# ExtensionConnector.net
KiCad netlist of a schematic drawn in Altium Designer
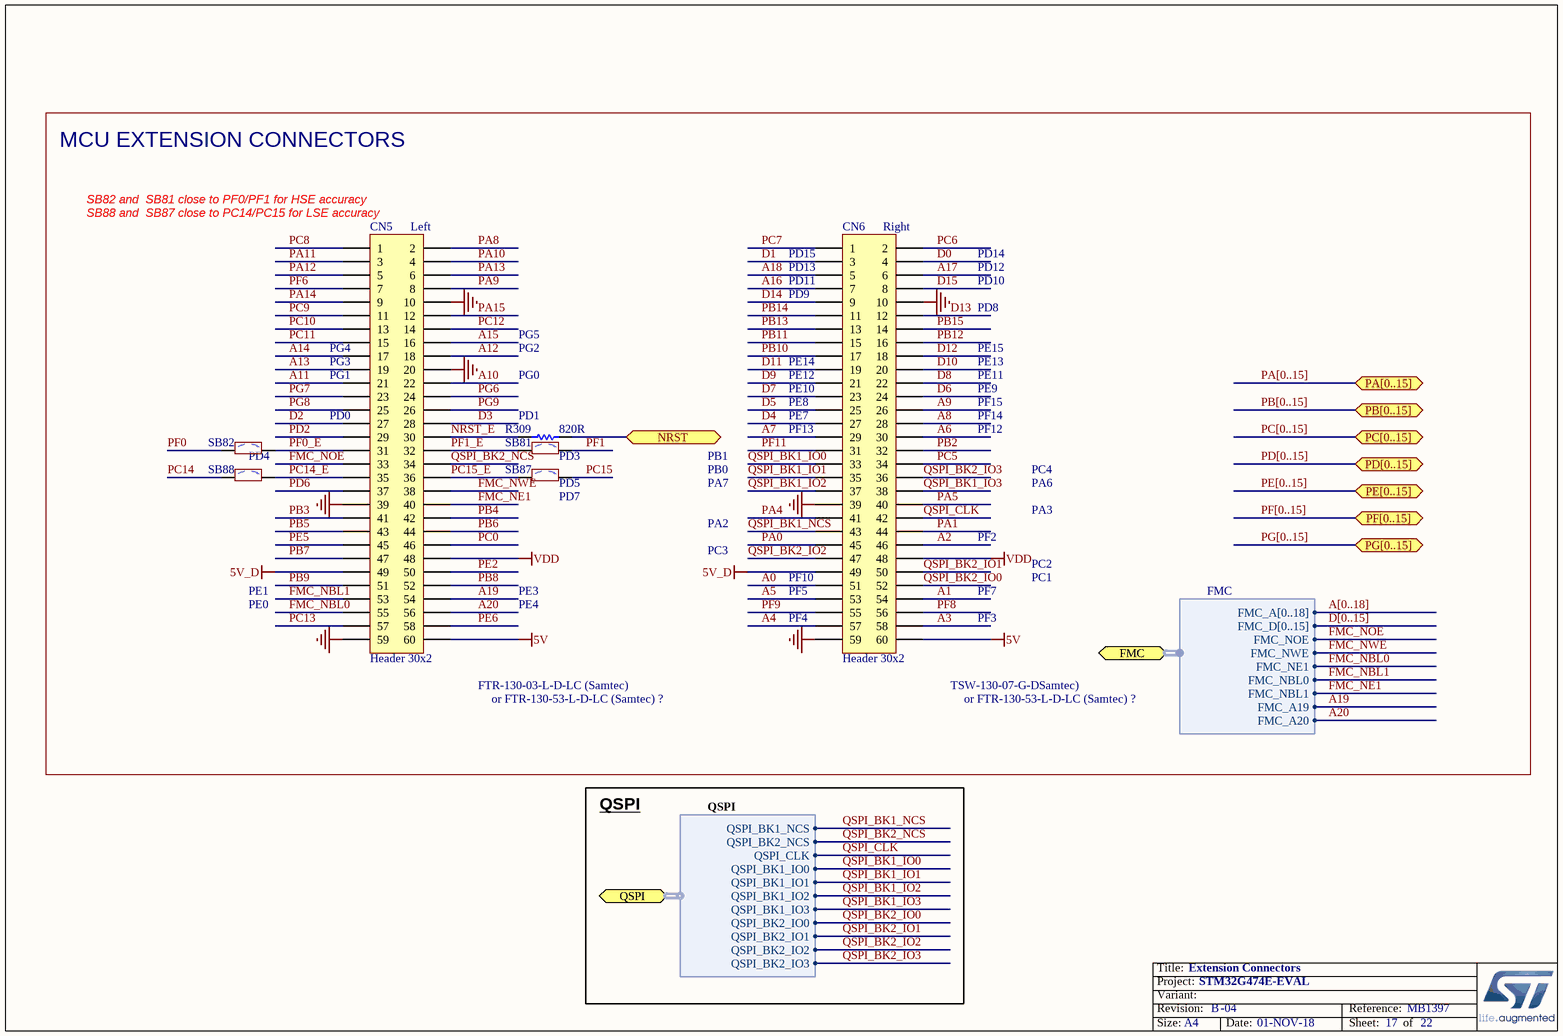
[diagram p0: ExtensionConnector.SchDoc]

(export (version "E")
  (design (tool "Eeschema 10.0.6"))
  (components
    (comp (ref "CN5")
      (value "Header 30x2")
      (footprint "CON_SAMTEC_FTR-130-53-L-D-LC")
      (description "Header 30x2, 1.27mm, VR, CMS, Height 7.24mm")
      (fields
        (field (name "INTERNAL_PART_NUMBER") "MCD-00576")
        (field (name "MANUFACTURER_PART_NUMBER") "FTR-130-53-L-D-LC")
        (field (name "PROVIDED_BY") "SUBCO")
      )
      (libsource (lib "MCD_PARTS_database") (part "Header 30x2"))
    )
    (comp (ref "CN6")
      (value "Header 30x2")
      (footprint "CON_SAMTEC_FTR-130-53-L-D-LC")
      (description "Header 30x2, 1.27mm, VR, CMS, Height 7.24mm")
      (fields
        (field (name "INTERNAL_PART_NUMBER") "MCD-00576")
        (field (name "MANUFACTURER_PART_NUMBER") "FTR-130-53-L-D-LC")
        (field (name "PROVIDED_BY") "SUBCO")
      )
      (libsource (lib "MCD_PARTS_database") (part "Header 30x2"))
    )
    (comp (ref "R309")
      (value "820R")
      (footprint "R0402")
      (description "Resistor,820R,0402,1%,1/16W")
      (fields
        (field (name "INTERNAL_PART_NUMBER") "MCD-00527")
        (field (name "MANUFACTURER_PART_NUMBER") "RC0402FR-07820RL")
        (field (name "PROVIDED_BY") "SUBCO")
      )
      (libsource (lib "MCD_PARTS_database") (part "Resistor"))
    )
    (comp (ref "SB81")
      (value "SB_OFF")
      (footprint "SOLDER-BRIDGE_R0603-0R")
      (description "Solder Bridge OFF")
      (fields
        (field (name "INTERNAL_PART_NUMBER") "MCD-00072")
        (field (name "MANUFACTURER_PART_NUMBER") "RC0603JR-070RL")
        (field (name "PROVIDED_BY") "SUBCO")
      )
      (libsource (lib "MCD_PARTS_database") (part "SB_OFF"))
    )
    (comp (ref "SB82")
      (value "SB_OFF")
      (footprint "SOLDER-BRIDGE_R0603-0R")
      (description "Solder Bridge OFF")
      (fields
        (field (name "INTERNAL_PART_NUMBER") "MCD-00072")
        (field (name "MANUFACTURER_PART_NUMBER") "RC0603JR-070RL")
        (field (name "PROVIDED_BY") "SUBCO")
      )
      (libsource (lib "MCD_PARTS_database") (part "SB_OFF"))
    )
    (comp (ref "SB87")
      (value "SB_OFF")
      (footprint "SOLDER-BRIDGE_R0603-0R")
      (description "Solder Bridge OFF")
      (fields
        (field (name "INTERNAL_PART_NUMBER") "MCD-00072")
        (field (name "MANUFACTURER_PART_NUMBER") "RC0603JR-070RL")
        (field (name "PROVIDED_BY") "SUBCO")
      )
      (libsource (lib "MCD_PARTS_database") (part "SB_OFF"))
    )
    (comp (ref "SB88")
      (value "SB_OFF")
      (footprint "SOLDER-BRIDGE_R0603-0R")
      (description "Solder Bridge OFF")
      (fields
        (field (name "INTERNAL_PART_NUMBER") "MCD-00072")
        (field (name "MANUFACTURER_PART_NUMBER") "RC0603JR-070RL")
        (field (name "PROVIDED_BY") "SUBCO")
      )
      (libsource (lib "MCD_PARTS_database") (part "SB_OFF"))
    )
  )
  (nets
    (net (code "62") (name "/A0") (class "Default")
      (node (ref "CN6") (pin "51") (pinfunction "51_51") (pintype "passive"))
    )
    (net (code "63") (name "/A1") (class "Default")
      (node (ref "CN6") (pin "54") (pinfunction "54_54") (pintype "passive"))
    )
    (net (code "64") (name "/A2") (class "Default")
      (node (ref "CN6") (pin "46") (pinfunction "46_46") (pintype "passive"))
    )
    (net (code "65") (name "/A3") (class "Default")
      (node (ref "CN6") (pin "58") (pinfunction "58_58") (pintype "passive"))
    )
    (net (code "66") (name "/A4") (class "Default")
      (node (ref "CN6") (pin "57") (pinfunction "57_57") (pintype "passive"))
    )
    (net (code "67") (name "/A5") (class "Default")
      (node (ref "CN6") (pin "53") (pinfunction "53_53") (pintype "passive"))
    )
    (net (code "68") (name "/A6") (class "Default")
      (node (ref "CN6") (pin "30") (pinfunction "30_30") (pintype "passive"))
    )
    (net (code "69") (name "/A7") (class "Default")
      (node (ref "CN6") (pin "29") (pinfunction "29_29") (pintype "passive"))
    )
    (net (code "70") (name "/A8") (class "Default")
      (node (ref "CN6") (pin "28") (pinfunction "28_28") (pintype "passive"))
    )
    (net (code "71") (name "/A9") (class "Default")
      (node (ref "CN6") (pin "26") (pinfunction "26_26") (pintype "passive"))
    )
    (net (code "72") (name "/A10") (class "Default")
      (node (ref "CN5") (pin "22") (pinfunction "22_22") (pintype "passive"))
    )
    (net (code "73") (name "/A11") (class "Default")
      (node (ref "CN5") (pin "21") (pinfunction "21_21") (pintype "passive"))
    )
    (net (code "74") (name "/A12") (class "Default")
      (node (ref "CN5") (pin "18") (pinfunction "18_18") (pintype "passive"))
    )
    (net (code "75") (name "/A13") (class "Default")
      (node (ref "CN5") (pin "19") (pinfunction "19_19") (pintype "passive"))
    )
    (net (code "76") (name "/A14") (class "Default")
      (node (ref "CN5") (pin "17") (pinfunction "17_17") (pintype "passive"))
    )
    (net (code "77") (name "/A15") (class "Default")
      (node (ref "CN5") (pin "16") (pinfunction "16_16") (pintype "passive"))
    )
    (net (code "78") (name "/A16") (class "Default")
      (node (ref "CN6") (pin "7") (pinfunction "7_7") (pintype "passive"))
    )
    (net (code "79") (name "/A17") (class "Default")
      (node (ref "CN6") (pin "6") (pinfunction "6_6") (pintype "passive"))
    )
    (net (code "80") (name "/A18") (class "Default")
      (node (ref "CN6") (pin "5") (pinfunction "5_5") (pintype "passive"))
    )
    (net (code "81") (name "/A19") (class "Default")
      (node (ref "CN5") (pin "54") (pinfunction "54_54") (pintype "passive"))
    )
    (net (code "82") (name "/A20") (class "Default")
      (node (ref "CN5") (pin "56") (pinfunction "56_56") (pintype "passive"))
    )
    (net (code "84") (name "/D0") (class "Default")
      (node (ref "CN6") (pin "4") (pinfunction "4_4") (pintype "passive"))
    )
    (net (code "85") (name "/D1") (class "Default")
      (node (ref "CN6") (pin "3") (pinfunction "3_3") (pintype "passive"))
    )
    (net (code "86") (name "/D2") (class "Default")
      (node (ref "CN5") (pin "27") (pinfunction "27_27") (pintype "passive"))
    )
    (net (code "87") (name "/D3") (class "Default")
      (node (ref "CN5") (pin "28") (pinfunction "28_28") (pintype "passive"))
    )
    (net (code "88") (name "/D4") (class "Default")
      (node (ref "CN6") (pin "27") (pinfunction "27_27") (pintype "passive"))
    )
    (net (code "89") (name "/D5") (class "Default")
      (node (ref "CN6") (pin "25") (pinfunction "25_25") (pintype "passive"))
    )
    (net (code "90") (name "/D6") (class "Default")
      (node (ref "CN6") (pin "24") (pinfunction "24_24") (pintype "passive"))
    )
    (net (code "91") (name "/D7") (class "Default")
      (node (ref "CN6") (pin "23") (pinfunction "23_23") (pintype "passive"))
    )
    (net (code "92") (name "/D8") (class "Default")
      (node (ref "CN6") (pin "22") (pinfunction "22_22") (pintype "passive"))
    )
    (net (code "93") (name "/D9") (class "Default")
      (node (ref "CN6") (pin "21") (pinfunction "21_21") (pintype "passive"))
    )
    (net (code "94") (name "/D10") (class "Default")
      (node (ref "CN6") (pin "20") (pinfunction "20_20") (pintype "passive"))
    )
    (net (code "95") (name "/D11") (class "Default")
      (node (ref "CN6") (pin "19") (pinfunction "19_19") (pintype "passive"))
    )
    (net (code "96") (name "/D12") (class "Default")
      (node (ref "CN6") (pin "18") (pinfunction "18_18") (pintype "passive"))
    )
    (net (code "97") (name "/D13") (class "Default")
      (node (ref "CN6") (pin "12") (pinfunction "12_12") (pintype "passive"))
    )
    (net (code "98") (name "/D14") (class "Default")
      (node (ref "CN6") (pin "9") (pinfunction "9_9") (pintype "passive"))
    )
    (net (code "99") (name "/D15") (class "Default")
      (node (ref "CN6") (pin "8") (pinfunction "8_8") (pintype "passive"))
    )
    (net (code "101") (name "/FMC_NBL0") (class "Default")
      (node (ref "CN5") (pin "55") (pinfunction "55_55") (pintype "passive"))
    )
    (net (code "102") (name "/FMC_NBL1") (class "Default")
      (node (ref "CN5") (pin "53") (pinfunction "53_53") (pintype "passive"))
    )
    (net (code "103") (name "/FMC_NE1") (class "Default")
      (node (ref "CN5") (pin "40") (pinfunction "40_40") (pintype "passive"))
    )
    (net (code "104") (name "/FMC_NOE") (class "Default")
      (node (ref "CN5") (pin "33") (pinfunction "33_33") (pintype "passive"))
    )
    (net (code "105") (name "/FMC_NWE") (class "Default")
      (node (ref "CN5") (pin "38") (pinfunction "38_38") (pintype "passive"))
    )
    (net (code "106") (name "/NRST") (class "Default")
      (node (ref "R309") (pin "2") (pinfunction "2_2") (pintype "passive"))
    )
    (net (code "107") (name "/NRST_E") (class "Default")
      (node (ref "CN5") (pin "30") (pinfunction "30_30") (pintype "passive"))
      (node (ref "R309") (pin "1") (pinfunction "1_1") (pintype "passive"))
    )
    (net (code "108") (name "/PA0") (class "Default")
      (node (ref "CN6") (pin "45") (pinfunction "45_45") (pintype "passive"))
    )
    (net (code "109") (name "/PA1") (class "Default")
      (node (ref "CN6") (pin "44") (pinfunction "44_44") (pintype "passive"))
    )
    (net (code "110") (name "/PA4") (class "Default")
      (node (ref "CN6") (pin "41") (pinfunction "41_41") (pintype "passive"))
    )
    (net (code "111") (name "/PA5") (class "Default")
      (node (ref "CN6") (pin "40") (pinfunction "40_40") (pintype "passive"))
    )
    (net (code "112") (name "/PA8") (class "Default")
      (node (ref "CN5") (pin "2") (pinfunction "2_2") (pintype "passive"))
    )
    (net (code "113") (name "/PA9") (class "Default")
      (node (ref "CN5") (pin "8") (pinfunction "8_8") (pintype "passive"))
    )
    (net (code "114") (name "/PA10") (class "Default")
      (node (ref "CN5") (pin "4") (pinfunction "4_4") (pintype "passive"))
    )
    (net (code "115") (name "/PA11") (class "Default")
      (node (ref "CN5") (pin "3") (pinfunction "3_3") (pintype "passive"))
    )
    (net (code "116") (name "/PA12") (class "Default")
      (node (ref "CN5") (pin "5") (pinfunction "5_5") (pintype "passive"))
    )
    (net (code "117") (name "/PA13") (class "Default")
      (node (ref "CN5") (pin "6") (pinfunction "6_6") (pintype "passive"))
    )
    (net (code "118") (name "/PA14") (class "Default")
      (node (ref "CN5") (pin "9") (pinfunction "9_9") (pintype "passive"))
    )
    (net (code "119") (name "/PA15") (class "Default")
      (node (ref "CN5") (pin "12") (pinfunction "12_12") (pintype "passive"))
    )
    (net (code "121") (name "/PB2") (class "Default")
      (node (ref "CN6") (pin "32") (pinfunction "32_32") (pintype "passive"))
    )
    (net (code "122") (name "/PB3") (class "Default")
      (node (ref "CN5") (pin "41") (pinfunction "41_41") (pintype "passive"))
    )
    (net (code "123") (name "/PB4") (class "Default")
      (node (ref "CN5") (pin "42") (pinfunction "42_42") (pintype "passive"))
    )
    (net (code "124") (name "/PB5") (class "Default")
      (node (ref "CN5") (pin "43") (pinfunction "43_43") (pintype "passive"))
    )
    (net (code "125") (name "/PB6") (class "Default")
      (node (ref "CN5") (pin "44") (pinfunction "44_44") (pintype "passive"))
    )
    (net (code "126") (name "/PB7") (class "Default")
      (node (ref "CN5") (pin "47") (pinfunction "47_47") (pintype "passive"))
    )
    (net (code "127") (name "/PB8") (class "Default")
      (node (ref "CN5") (pin "52") (pinfunction "52_52") (pintype "passive"))
    )
    (net (code "128") (name "/PB9") (class "Default")
      (node (ref "CN5") (pin "51") (pinfunction "51_51") (pintype "passive"))
    )
    (net (code "129") (name "/PB10") (class "Default")
      (node (ref "CN6") (pin "17") (pinfunction "17_17") (pintype "passive"))
    )
    (net (code "130") (name "/PB11") (class "Default")
      (node (ref "CN6") (pin "15") (pinfunction "15_15") (pintype "passive"))
    )
    (net (code "131") (name "/PB12") (class "Default")
      (node (ref "CN6") (pin "16") (pinfunction "16_16") (pintype "passive"))
    )
    (net (code "132") (name "/PB13") (class "Default")
      (node (ref "CN6") (pin "13") (pinfunction "13_13") (pintype "passive"))
    )
    (net (code "133") (name "/PB14") (class "Default")
      (node (ref "CN6") (pin "11") (pinfunction "11_11") (pintype "passive"))
    )
    (net (code "134") (name "/PB15") (class "Default")
      (node (ref "CN6") (pin "14") (pinfunction "14_14") (pintype "passive"))
    )
    (net (code "136") (name "/PC0") (class "Default")
      (node (ref "CN5") (pin "46") (pinfunction "46_46") (pintype "passive"))
    )
    (net (code "137") (name "/PC5") (class "Default")
      (node (ref "CN6") (pin "34") (pinfunction "34_34") (pintype "passive"))
    )
    (net (code "138") (name "/PC6") (class "Default")
      (node (ref "CN6") (pin "2") (pinfunction "2_2") (pintype "passive"))
    )
    (net (code "139") (name "/PC7") (class "Default")
      (node (ref "CN6") (pin "1") (pinfunction "1_1") (pintype "passive"))
    )
    (net (code "140") (name "/PC8") (class "Default")
      (node (ref "CN5") (pin "1") (pinfunction "1_1") (pintype "passive"))
    )
    (net (code "141") (name "/PC9") (class "Default")
      (node (ref "CN5") (pin "11") (pinfunction "11_11") (pintype "passive"))
    )
    (net (code "142") (name "/PC10") (class "Default")
      (node (ref "CN5") (pin "13") (pinfunction "13_13") (pintype "passive"))
    )
    (net (code "143") (name "/PC11") (class "Default")
      (node (ref "CN5") (pin "15") (pinfunction "15_15") (pintype "passive"))
    )
    (net (code "144") (name "/PC12") (class "Default")
      (node (ref "CN5") (pin "14") (pinfunction "14_14") (pintype "passive"))
    )
    (net (code "145") (name "/PC13") (class "Default")
      (node (ref "CN5") (pin "57") (pinfunction "57_57") (pintype "passive"))
    )
    (net (code "146") (name "/PC14") (class "Default")
      (node (ref "SB88") (pin "1") (pinfunction "1_1") (pintype "passive"))
    )
    (net (code "147") (name "/PC14_E") (class "Default")
      (node (ref "CN5") (pin "35") (pinfunction "35_35") (pintype "passive"))
      (node (ref "SB88") (pin "2") (pinfunction "2_2") (pintype "passive"))
    )
    (net (code "148") (name "/PC15") (class "Default")
      (node (ref "SB87") (pin "2") (pinfunction "2_2") (pintype "passive"))
    )
    (net (code "149") (name "/PC15_E") (class "Default")
      (node (ref "CN5") (pin "36") (pinfunction "36_36") (pintype "passive"))
      (node (ref "SB87") (pin "1") (pinfunction "1_1") (pintype "passive"))
    )
    (net (code "151") (name "/PD2") (class "Default")
      (node (ref "CN5") (pin "29") (pinfunction "29_29") (pintype "passive"))
    )
    (net (code "152") (name "/PD6") (class "Default")
      (node (ref "CN5") (pin "37") (pinfunction "37_37") (pintype "passive"))
    )
    (net (code "154") (name "/PE2") (class "Default")
      (node (ref "CN5") (pin "50") (pinfunction "50_50") (pintype "passive"))
    )
    (net (code "155") (name "/PE5") (class "Default")
      (node (ref "CN5") (pin "45") (pinfunction "45_45") (pintype "passive"))
    )
    (net (code "156") (name "/PE6") (class "Default")
      (node (ref "CN5") (pin "58") (pinfunction "58_58") (pintype "passive"))
    )
    (net (code "158") (name "/PF0") (class "Default")
      (node (ref "SB82") (pin "1") (pinfunction "1_1") (pintype "passive"))
    )
    (net (code "159") (name "/PF0_E") (class "Default")
      (node (ref "CN5") (pin "31") (pinfunction "31_31") (pintype "passive"))
      (node (ref "SB82") (pin "2") (pinfunction "2_2") (pintype "passive"))
    )
    (net (code "160") (name "/PF1") (class "Default")
      (node (ref "SB81") (pin "2") (pinfunction "2_2") (pintype "passive"))
    )
    (net (code "161") (name "/PF1_E") (class "Default")
      (node (ref "CN5") (pin "32") (pinfunction "32_32") (pintype "passive"))
      (node (ref "SB81") (pin "1") (pinfunction "1_1") (pintype "passive"))
    )
    (net (code "162") (name "/PF6") (class "Default")
      (node (ref "CN5") (pin "7") (pinfunction "7_7") (pintype "passive"))
    )
    (net (code "163") (name "/PF8") (class "Default")
      (node (ref "CN6") (pin "56") (pinfunction "56_56") (pintype "passive"))
    )
    (net (code "164") (name "/PF9") (class "Default")
      (node (ref "CN6") (pin "55") (pinfunction "55_55") (pintype "passive"))
    )
    (net (code "165") (name "/PF11") (class "Default")
      (node (ref "CN6") (pin "31") (pinfunction "31_31") (pintype "passive"))
    )
    (net (code "167") (name "/PG6") (class "Default")
      (node (ref "CN5") (pin "24") (pinfunction "24_24") (pintype "passive"))
    )
    (net (code "168") (name "/PG7") (class "Default")
      (node (ref "CN5") (pin "23") (pinfunction "23_23") (pintype "passive"))
    )
    (net (code "169") (name "/PG8") (class "Default")
      (node (ref "CN5") (pin "25") (pinfunction "25_25") (pintype "passive"))
    )
    (net (code "170") (name "/PG9") (class "Default")
      (node (ref "CN5") (pin "26") (pinfunction "26_26") (pintype "passive"))
    )
    (net (code "172") (name "/QSPI_BK1_IO0") (class "Default")
      (node (ref "CN6") (pin "33") (pinfunction "33_33") (pintype "passive"))
    )
    (net (code "173") (name "/QSPI_BK1_IO1") (class "Default")
      (node (ref "CN6") (pin "35") (pinfunction "35_35") (pintype "passive"))
    )
    (net (code "174") (name "/QSPI_BK1_IO2") (class "Default")
      (node (ref "CN6") (pin "37") (pinfunction "37_37") (pintype "passive"))
    )
    (net (code "175") (name "/QSPI_BK1_IO3") (class "Default")
      (node (ref "CN6") (pin "38") (pinfunction "38_38") (pintype "passive"))
    )
    (net (code "176") (name "/QSPI_BK1_NCS") (class "Default")
      (node (ref "CN6") (pin "43") (pinfunction "43_43") (pintype "passive"))
    )
    (net (code "177") (name "/QSPI_BK2_IO0") (class "Default")
      (node (ref "CN6") (pin "52") (pinfunction "52_52") (pintype "passive"))
    )
    (net (code "178") (name "/QSPI_BK2_IO1") (class "Default")
      (node (ref "CN6") (pin "50") (pinfunction "50_50") (pintype "passive"))
    )
    (net (code "179") (name "/QSPI_BK2_IO2") (class "Default")
      (node (ref "CN6") (pin "47") (pinfunction "47_47") (pintype "passive"))
    )
    (net (code "180") (name "/QSPI_BK2_IO3") (class "Default")
      (node (ref "CN6") (pin "36") (pinfunction "36_36") (pintype "passive"))
    )
    (net (code "181") (name "/QSPI_BK2_NCS") (class "Default")
      (node (ref "CN5") (pin "34") (pinfunction "34_34") (pintype "passive"))
    )
    (net (code "182") (name "/QSPI_CLK") (class "Default")
      (node (ref "CN6") (pin "42") (pinfunction "42_42") (pintype "passive"))
    )
    (net (code "185") (name "5V") (class "Default")
      (node (ref "CN5") (pin "60") (pinfunction "60_60") (pintype "passive"))
      (node (ref "CN6") (pin "60") (pinfunction "60_60") (pintype "passive"))
    )
    (net (code "186") (name "5V_D") (class "Default")
      (node (ref "CN5") (pin "49") (pinfunction "49_49") (pintype "passive"))
      (node (ref "CN6") (pin "49") (pinfunction "49_49") (pintype "passive"))
    )
    (net (code "187") (name "GND") (class "Default")
      (node (ref "CN5") (pin "10") (pinfunction "10_10") (pintype "passive"))
      (node (ref "CN5") (pin "20") (pinfunction "20_20") (pintype "passive"))
      (node (ref "CN5") (pin "39") (pinfunction "39_39") (pintype "passive"))
      (node (ref "CN5") (pin "59") (pinfunction "59_59") (pintype "passive"))
      (node (ref "CN6") (pin "10") (pinfunction "10_10") (pintype "passive"))
      (node (ref "CN6") (pin "39") (pinfunction "39_39") (pintype "passive"))
      (node (ref "CN6") (pin "59") (pinfunction "59_59") (pintype "passive"))
    )
    (net (code "188") (name "VDD") (class "Default")
      (node (ref "CN5") (pin "48") (pinfunction "48_48") (pintype "passive"))
      (node (ref "CN6") (pin "48") (pinfunction "48_48") (pintype "passive"))
    )
  )
)
